# tube_power.net
KiCad netlist of a schematic drawn in EAGLE
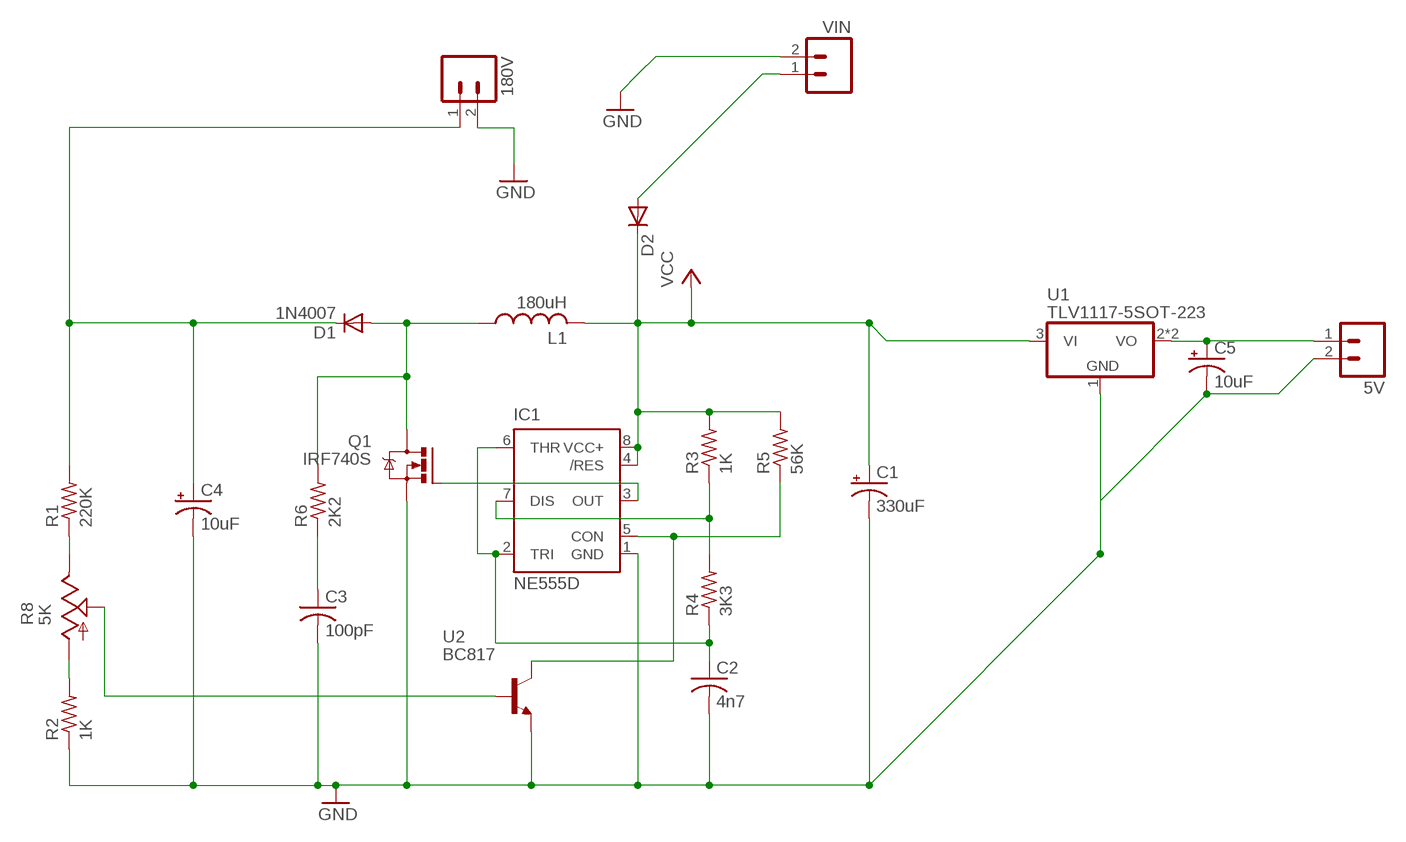
[diagram p0: schematic, sheet 1]

(export (version "E")
  (design (tool "Eeschema 10.0.6"))
  (components
    (comp (ref "5V")
      (value "M023.5MM")
      (footprint "eagle-import:SCREWTERMINAL-3.5MM-2")
      (libsource (lib "eagle-import") (part "M023.5MM"))
    )
    (comp (ref "180V")
      (value "M023.5MM")
      (footprint "eagle-import:SCREWTERMINAL-3.5MM-2")
      (libsource (lib "eagle-import") (part "M023.5MM"))
    )
    (comp (ref "C1")
      (value "330uF")
      (footprint "eagle-import:E5-10,5")
      (libsource (lib "eagle-import") (part "CAPACITOR_POLE5-10.5"))
    )
    (comp (ref "C2")
      (value "4n7")
      (footprint "eagle-import:C0805K")
      (libsource (lib "eagle-import") (part "CAPACITORC0805K"))
    )
    (comp (ref "C3")
      (value "100pF")
      (footprint "eagle-import:C0805K")
      (libsource (lib "eagle-import") (part "CAPACITORC0805K"))
    )
    (comp (ref "C4")
      (value "10uF")
      (footprint "eagle-import:E3,5-8")
      (libsource (lib "eagle-import") (part "CAPACITOR_POLE3.5-8"))
    )
    (comp (ref "C5")
      (value "10uF")
      (footprint "eagle-import:E2-5")
      (libsource (lib "eagle-import") (part "CAPACITOR_POLE2-5"))
    )
    (comp (ref "D1")
      (value "1N4007")
      (footprint "eagle-import:SMA-DIODE")
      (libsource (lib "eagle-import") (part "DIODESMA"))
    )
    (comp (ref "D2")
      (value "DIODESOD-80")
      (footprint "eagle-import:SOD80C")
      (libsource (lib "eagle-import") (part "DIODESOD-80"))
    )
    (comp (ref "IC1")
      (value "NE555D")
      (footprint "eagle-import:SO08")
      (libsource (lib "eagle-import") (part "NE555D"))
    )
    (comp (ref "L1")
      (value "180uH")
      (footprint "eagle-import:RBL0712")
      (libsource (lib "eagle-import") (part "INDUCTOR"))
    )
    (comp (ref "Q1")
      (value "IRF740S")
      (footprint "eagle-import:TO263")
      (libsource (lib "eagle-import") (part "IRF740S"))
    )
    (comp (ref "R1")
      (value "220K")
      (footprint "eagle-import:0207_10")
      (libsource (lib "eagle-import") (part "RESISTOR0207/10"))
    )
    (comp (ref "R2")
      (value "1K")
      (footprint "eagle-import:R1206")
      (libsource (lib "eagle-import") (part "RESISTORR1206"))
    )
    (comp (ref "R3")
      (value "1K")
      (footprint "eagle-import:R0805")
      (libsource (lib "eagle-import") (part "RESISTORR0805"))
    )
    (comp (ref "R4")
      (value "3K3")
      (footprint "eagle-import:R0805")
      (libsource (lib "eagle-import") (part "RESISTORR0805"))
    )
    (comp (ref "R5")
      (value "56K")
      (footprint "eagle-import:R0805")
      (libsource (lib "eagle-import") (part "RESISTORR0805"))
    )
    (comp (ref "R6")
      (value "2K2")
      (footprint "eagle-import:R0805")
      (libsource (lib "eagle-import") (part "RESISTORR0805"))
    )
    (comp (ref "R8")
      (value "5K")
      (footprint "eagle-import:TRIM-EVM2N")
      (libsource (lib "eagle-import") (part "TRIM_POTEVM2N"))
    )
    (comp (ref "U1")
      (value "TLV1117-5SOT-223")
      (footprint "eagle-import:SOT-223")
      (libsource (lib "eagle-import") (part "TLV1117-5SOT-223"))
    )
    (comp (ref "U2")
      (value "BC817")
      (footprint "eagle-import:SOT-23")
      (libsource (lib "eagle-import") (part "BC817"))
    )
    (comp (ref "VIN")
      (value "M023.5MM")
      (footprint "eagle-import:SCREWTERMINAL-3.5MM-2")
      (libsource (lib "eagle-import") (part "M023.5MM"))
    )
  )
  (nets
    (net (code "1") (name "GND") (class "Default")
      (node (ref "180V") (pin "2") (pinfunction "2_2") (pintype "passive"))
      (node (ref "5V") (pin "2") (pinfunction "2_2") (pintype "passive"))
      (node (ref "C1") (pin "-") (pinfunction "-_-") (pintype "passive"))
      (node (ref "C2") (pin "2") (pinfunction "2_2") (pintype "passive"))
      (node (ref "C3") (pin "2") (pinfunction "2_2") (pintype "passive"))
      (node (ref "C4") (pin "-") (pinfunction "-_-") (pintype "passive"))
      (node (ref "C5") (pin "-") (pinfunction "-_-") (pintype "passive"))
      (node (ref "IC1") (pin "1") (pinfunction "GND_1") (pintype "power_in"))
      (node (ref "Q1") (pin "2") (pinfunction "S_2") (pintype "passive"))
      (node (ref "R2") (pin "1") (pinfunction "1_1") (pintype "passive"))
      (node (ref "U1") (pin "1") (pinfunction "GND_1") (pintype "passive"))
      (node (ref "U2") (pin "2") (pinfunction "E_2") (pintype "passive"))
      (node (ref "VIN") (pin "2") (pinfunction "2_2") (pintype "passive"))
    )
    (net (code "2") (name "Net-(5V-Pad1)") (class "Default")
      (node (ref "5V") (pin "1") (pinfunction "1_1") (pintype "passive"))
      (node (ref "C5") (pin "+") (pinfunction "+_+") (pintype "passive"))
      (node (ref "U1") (pin "2") (pinfunction "VO_2") (pintype "passive"))
      (node (ref "U1") (pin "4") (pinfunction "VO_4") (pintype "passive"))
    )
    (net (code "3") (name "Net-(180V-Pad1)") (class "Default")
      (node (ref "180V") (pin "1") (pinfunction "1_1") (pintype "passive"))
      (node (ref "C4") (pin "+") (pinfunction "+_+") (pintype "passive"))
      (node (ref "D1") (pin "C") (pinfunction "C_C") (pintype "passive"))
      (node (ref "R1") (pin "2") (pinfunction "2_2") (pintype "passive"))
    )
    (net (code "4") (name "Net-(C3-Pad1)") (class "Default")
      (node (ref "C3") (pin "1") (pinfunction "1_1") (pintype "passive"))
      (node (ref "R6") (pin "1") (pinfunction "1_1") (pintype "passive"))
    )
    (net (code "5") (name "Net-(D2-PadA)") (class "Default")
      (node (ref "D2") (pin "A") (pinfunction "A_A") (pintype "passive"))
      (node (ref "VIN") (pin "1") (pinfunction "1_1") (pintype "passive"))
    )
    (net (code "6") (name "Net-(IC1-CON)") (class "Default")
      (node (ref "IC1") (pin "5") (pinfunction "CON_5") (pintype "input"))
      (node (ref "R5") (pin "1") (pinfunction "1_1") (pintype "passive"))
      (node (ref "U2") (pin "3") (pinfunction "C_3") (pintype "passive"))
    )
    (net (code "7") (name "Net-(IC1-DIS)") (class "Default")
      (node (ref "IC1") (pin "7") (pinfunction "DIS_7") (pintype "input"))
      (node (ref "R3") (pin "1") (pinfunction "1_1") (pintype "passive"))
      (node (ref "R4") (pin "2") (pinfunction "2_2") (pintype "passive"))
    )
    (net (code "8") (name "Net-(IC1-OUT)") (class "Default")
      (node (ref "IC1") (pin "3") (pinfunction "OUT_3") (pintype "output"))
      (node (ref "Q1") (pin "1") (pinfunction "G_1") (pintype "passive"))
    )
    (net (code "9") (name "Net-(IC1-THR)") (class "Default")
      (node (ref "C2") (pin "1") (pinfunction "1_1") (pintype "passive"))
      (node (ref "IC1") (pin "2") (pinfunction "TRI_2") (pintype "input"))
      (node (ref "IC1") (pin "6") (pinfunction "THR_6") (pintype "input"))
      (node (ref "R4") (pin "1") (pinfunction "1_1") (pintype "passive"))
    )
    (net (code "10") (name "Net-(L1-1)") (class "Default")
      (node (ref "D1") (pin "A") (pinfunction "A_A") (pintype "passive"))
      (node (ref "L1") (pin "P$1") (pinfunction "1_P$1") (pintype "passive"))
      (node (ref "Q1") (pin "3") (pinfunction "D_3") (pintype "passive"))
      (node (ref "R6") (pin "2") (pinfunction "2_2") (pintype "passive"))
    )
    (net (code "11") (name "Net-(R8-A)") (class "Default")
      (node (ref "R2") (pin "2") (pinfunction "2_2") (pintype "passive"))
      (node (ref "R8") (pin "P$1") (pinfunction "A_P$1") (pintype "passive"))
    )
    (net (code "12") (name "Net-(R8-E)") (class "Default")
      (node (ref "R1") (pin "1") (pinfunction "1_1") (pintype "passive"))
      (node (ref "R8") (pin "P$3") (pinfunction "E_P$3") (pintype "passive"))
    )
    (net (code "13") (name "Net-(R8-S)") (class "Default")
      (node (ref "R8") (pin "P$2") (pinfunction "S_P$2") (pintype "passive"))
      (node (ref "U2") (pin "1") (pinfunction "B_1") (pintype "passive"))
    )
    (net (code "14") (name "VCC") (class "Default")
      (node (ref "C1") (pin "+") (pinfunction "+_+") (pintype "passive"))
      (node (ref "D2") (pin "C") (pinfunction "C_C") (pintype "passive"))
      (node (ref "IC1") (pin "4") (pinfunction "/RES_4") (pintype "input"))
      (node (ref "IC1") (pin "8") (pinfunction "VCC+_8") (pintype "power_in"))
      (node (ref "L1") (pin "P$2") (pinfunction "2_P$2") (pintype "passive"))
      (node (ref "R3") (pin "2") (pinfunction "2_2") (pintype "passive"))
      (node (ref "R5") (pin "2") (pinfunction "2_2") (pintype "passive"))
      (node (ref "U1") (pin "3") (pinfunction "VI_3") (pintype "input"))
    )
  )
)
